# Talko_1_2.net
KiCad netlist of a schematic drawn in EAGLE
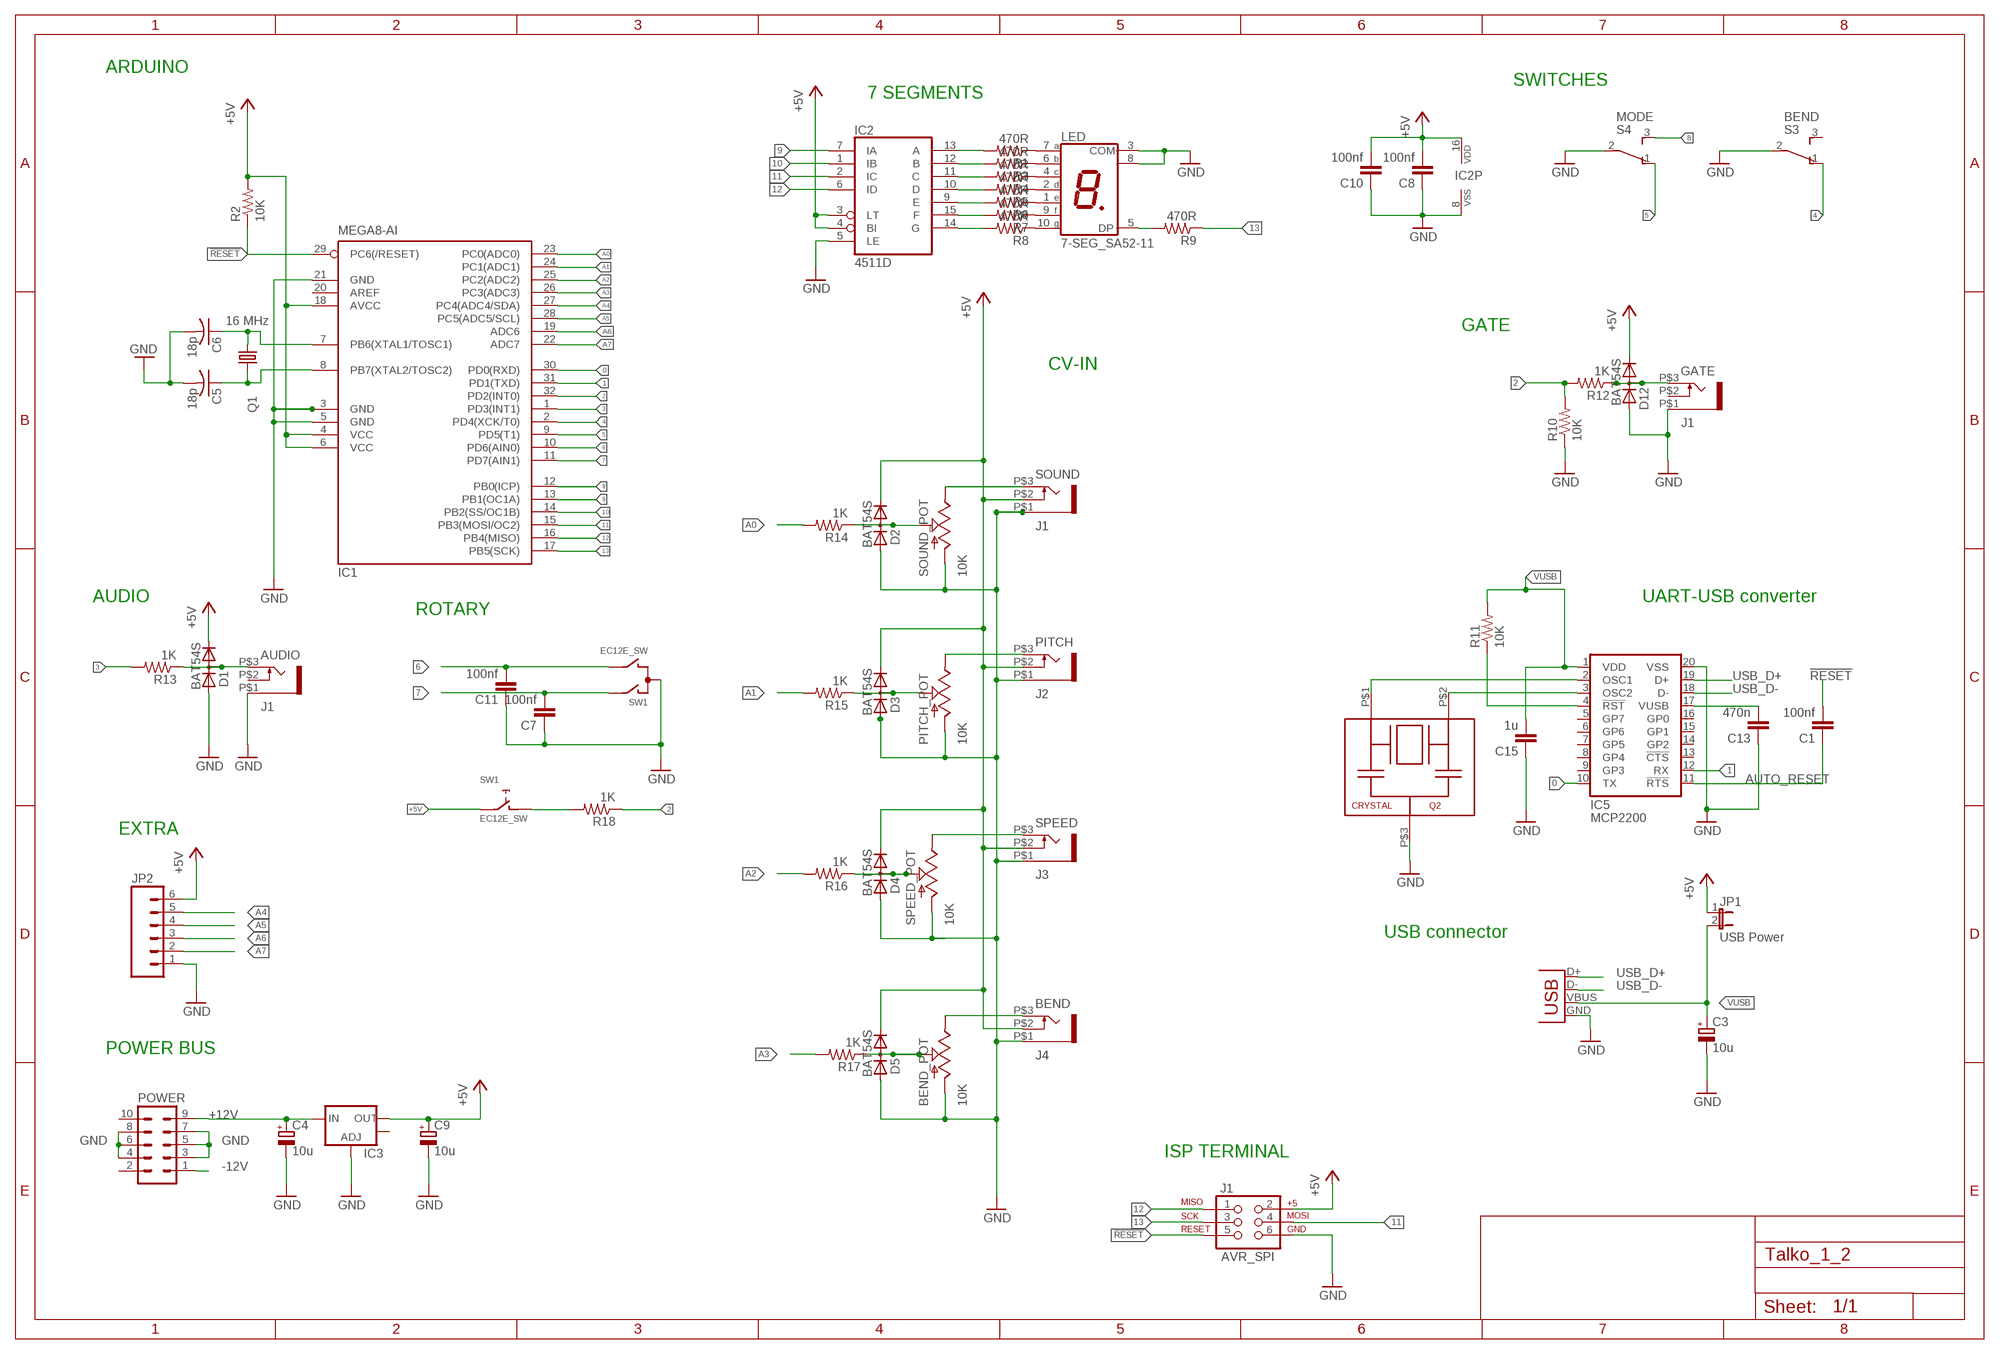
[diagram p0: schematic, sheet 1]

(export (version "E")
  (design (tool "Eeschema 10.0.6"))
  (components
    (comp (ref "AUDIO")
      (value "J1")
      (footprint "eagle-import:THONKICONN")
      (libsource (lib "eagle-import") (part "THONKICONN"))
    )
    (comp (ref "BEND")
      (value "J4")
      (footprint "eagle-import:THONKICONN")
      (libsource (lib "eagle-import") (part "THONKICONN"))
    )
    (comp (ref "BEND_POT")
      (value "10K")
      (footprint "eagle-import:ALPS_POT")
      (libsource (lib "eagle-import") (part "POT"))
    )
    (comp (ref "C1")
      (value "100nf")
      (footprint "eagle-import:C0805")
      (libsource (lib "eagle-import") (part "C-EUC0805"))
    )
    (comp (ref "C3")
      (value "10u")
      (footprint "eagle-import:R_2012-12R")
      (libsource (lib "eagle-import") (part "CPOL-EUR/2012-12R"))
    )
    (comp (ref "C4")
      (value "10u")
      (footprint "eagle-import:R_2012-12R")
      (libsource (lib "eagle-import") (part "CPOL-EUR/2012-12R"))
    )
    (comp (ref "C5")
      (value "18p")
      (footprint "eagle-import:C0805K")
      (libsource (lib "eagle-import") (part "C-USC0805K"))
    )
    (comp (ref "C6")
      (value "18p")
      (footprint "eagle-import:C0805K")
      (libsource (lib "eagle-import") (part "C-USC0805K"))
    )
    (comp (ref "C7")
      (value "100nf")
      (footprint "eagle-import:C0805")
      (libsource (lib "eagle-import") (part "C-EUC0805"))
    )
    (comp (ref "C8")
      (value "100nf")
      (footprint "eagle-import:C0805")
      (libsource (lib "eagle-import") (part "C-EUC0805"))
    )
    (comp (ref "C9")
      (value "10u")
      (footprint "eagle-import:R_2012-12R")
      (libsource (lib "eagle-import") (part "CPOL-EUR/2012-12R"))
    )
    (comp (ref "C10")
      (value "100nf")
      (footprint "eagle-import:C0805")
      (libsource (lib "eagle-import") (part "C-EUC0805"))
    )
    (comp (ref "C11")
      (value "100nf")
      (footprint "eagle-import:C0805")
      (libsource (lib "eagle-import") (part "C-EUC0805"))
    )
    (comp (ref "C13")
      (value "470n")
      (footprint "eagle-import:0805")
      (libsource (lib "eagle-import") (part "CAP0805"))
    )
    (comp (ref "C15")
      (value "1u")
      (footprint "eagle-import:0805")
      (libsource (lib "eagle-import") (part "CAP0805"))
    )
    (comp (ref "D1")
      (value "BAT54S")
      (footprint "eagle-import:SOT23")
      (libsource (lib "eagle-import") (part "DIODE_2CACA-SOT23"))
    )
    (comp (ref "D2")
      (value "BAT54S")
      (footprint "eagle-import:SOT23")
      (libsource (lib "eagle-import") (part "DIODE_2CACA-SOT23"))
    )
    (comp (ref "D3")
      (value "BAT54S")
      (footprint "eagle-import:SOT23")
      (libsource (lib "eagle-import") (part "DIODE_2CACA-SOT23"))
    )
    (comp (ref "D4")
      (value "BAT54S")
      (footprint "eagle-import:SOT23")
      (libsource (lib "eagle-import") (part "DIODE_2CACA-SOT23"))
    )
    (comp (ref "D5")
      (value "BAT54S")
      (footprint "eagle-import:SOT23")
      (libsource (lib "eagle-import") (part "DIODE_2CACA-SOT23"))
    )
    (comp (ref "D12")
      (value "BAT54S")
      (footprint "eagle-import:SOT23")
      (libsource (lib "eagle-import") (part "DIODE_2CACA-SOT23"))
    )
    (comp (ref "GATE")
      (value "J1")
      (footprint "eagle-import:THONKICONN")
      (libsource (lib "eagle-import") (part "THONKICONN"))
    )
    (comp (ref "IC1")
      (value "MEGA8-AI")
      (footprint "eagle-import:TQFP32-08")
      (fields (field (name "MPN") "ATMEGA8-16AU"))
      (libsource (lib "eagle-import") (part "MEGA8-AI"))
    )
    (comp (ref "IC2")
      (value "4511D")
      (footprint "eagle-import:SO16")
      (fields (field (name "OC_MOUSER") "863-MC14511BDG"))
      (libsource (lib "eagle-import") (part "4511D"))
    )
    (comp (ref "IC3")
      (value "V_REG_LM1117SOT223")
      (footprint "eagle-import:SOT223")
      (libsource (lib "eagle-import") (part "V_REG_LM1117SOT223"))
    )
    (comp (ref "IC5")
      (value "MCP2200")
      (footprint "eagle-import:SO20")
      (libsource (lib "eagle-import") (part "MCP2200"))
    )
    (comp (ref "J1")
      (value "AVR_SPI")
      (footprint "eagle-import:2X3_LOCK")
      (libsource (lib "eagle-import") (part "AVR_SPI_PRG_62X3_LOCK"))
    )
    (comp (ref "JP1")
      (value "USB Power")
      (footprint "eagle-import:JP1")
      (libsource (lib "eagle-import") (part "JP1E"))
    )
    (comp (ref "JP2")
      (value "M06SIP")
      (footprint "eagle-import:1X06")
      (libsource (lib "eagle-import") (part "M06SIP"))
    )
    (comp (ref "LED")
      (value "7-SEG_SA52-11")
      (footprint "eagle-import:SA52-11")
      (fields (field (name "OC_FARNELL") "1168602"))
      (libsource (lib "eagle-import") (part "7-SEG_SA52-11"))
    )
    (comp (ref "PITCH")
      (value "J2")
      (footprint "eagle-import:THONKICONN")
      (libsource (lib "eagle-import") (part "THONKICONN"))
    )
    (comp (ref "PITCH_POT")
      (value "10K")
      (footprint "eagle-import:ALPS_POT")
      (libsource (lib "eagle-import") (part "POT"))
    )
    (comp (ref "POWER")
      (value "10_PIN_HEADER")
      (footprint "eagle-import:MA05-2")
      (libsource (lib "eagle-import") (part "10_PIN_HEADER"))
    )
    (comp (ref "Q1")
      (value "16 MHz")
      (footprint "eagle-import:CTS406")
      (libsource (lib "eagle-import") (part "CRYSTALCTS406"))
    )
    (comp (ref "Q2")
      (value "CRYSTAL")
      (footprint "eagle-import:CRYSTAL")
      (libsource (lib "eagle-import") (part "CRYSTAL"))
    )
    (comp (ref "R1")
      (value "470R")
      (footprint "eagle-import:M0805")
      (libsource (lib "eagle-import") (part "R-US_M0805"))
    )
    (comp (ref "R2")
      (value "10K")
      (footprint "eagle-import:M0805")
      (libsource (lib "eagle-import") (part "R-US_M0805"))
    )
    (comp (ref "R3")
      (value "470R")
      (footprint "eagle-import:M0805")
      (libsource (lib "eagle-import") (part "R-US_M0805"))
    )
    (comp (ref "R4")
      (value "470R")
      (footprint "eagle-import:M0805")
      (libsource (lib "eagle-import") (part "R-US_M0805"))
    )
    (comp (ref "R5")
      (value "470R")
      (footprint "eagle-import:M0805")
      (libsource (lib "eagle-import") (part "R-US_M0805"))
    )
    (comp (ref "R6")
      (value "470R")
      (footprint "eagle-import:M0805")
      (libsource (lib "eagle-import") (part "R-US_M0805"))
    )
    (comp (ref "R7")
      (value "470R")
      (footprint "eagle-import:M0805")
      (libsource (lib "eagle-import") (part "R-US_M0805"))
    )
    (comp (ref "R8")
      (value "470R")
      (footprint "eagle-import:M0805")
      (libsource (lib "eagle-import") (part "R-US_M0805"))
    )
    (comp (ref "R9")
      (value "470R")
      (footprint "eagle-import:M0805")
      (libsource (lib "eagle-import") (part "R-US_M0805"))
    )
    (comp (ref "R10")
      (value "10K")
      (footprint "eagle-import:M0805")
      (libsource (lib "eagle-import") (part "R-US_M0805"))
    )
    (comp (ref "R11")
      (value "10K")
      (footprint "eagle-import:M0805")
      (libsource (lib "eagle-import") (part "R-US_M0805"))
    )
    (comp (ref "R12")
      (value "1K")
      (footprint "eagle-import:M0805")
      (libsource (lib "eagle-import") (part "R-US_M0805"))
    )
    (comp (ref "R13")
      (value "1K")
      (footprint "eagle-import:M0805")
      (libsource (lib "eagle-import") (part "R-US_M0805"))
    )
    (comp (ref "R14")
      (value "1K")
      (footprint "eagle-import:M0805")
      (libsource (lib "eagle-import") (part "R-US_M0805"))
    )
    (comp (ref "R15")
      (value "1K")
      (footprint "eagle-import:M0805")
      (libsource (lib "eagle-import") (part "R-US_M0805"))
    )
    (comp (ref "R16")
      (value "1K")
      (footprint "eagle-import:M0805")
      (libsource (lib "eagle-import") (part "R-US_M0805"))
    )
    (comp (ref "R17")
      (value "1K")
      (footprint "eagle-import:M0805")
      (libsource (lib "eagle-import") (part "R-US_M0805"))
    )
    (comp (ref "R18")
      (value "1K")
      (footprint "eagle-import:M0805")
      (libsource (lib "eagle-import") (part "R-US_M0805"))
    )
    (comp (ref "S3")
      (value "BEND")
      (footprint "eagle-import:TL3XPO")
      (libsource (lib "eagle-import") (part "TL36PO"))
    )
    (comp (ref "S4")
      (value "MODE")
      (footprint "eagle-import:TL3XPO")
      (libsource (lib "eagle-import") (part "TL36PO"))
    )
    (comp (ref "SOUND")
      (value "J1")
      (footprint "eagle-import:THONKICONN")
      (libsource (lib "eagle-import") (part "THONKICONN"))
    )
    (comp (ref "SOUND_POT")
      (value "10K")
      (footprint "eagle-import:ALPS_POT")
      (libsource (lib "eagle-import") (part "POT"))
    )
    (comp (ref "SPEED")
      (value "J3")
      (footprint "eagle-import:THONKICONN")
      (libsource (lib "eagle-import") (part "THONKICONN"))
    )
    (comp (ref "SPEED_POT")
      (value "10K")
      (footprint "eagle-import:ALPS_POT")
      (libsource (lib "eagle-import") (part "POT"))
    )
    (comp (ref "SW1")
      (value "EC12E_SW")
      (footprint "eagle-import:ALPS_EC12E_SW")
      (fields (field (name "MPN") "EC12E2424407") (field (name "OC_MOUSER") " PEC11R-4215K-S0024"))
      (libsource (lib "eagle-import") (part "EC12E_SW"))
    )
    (comp (ref "X3")
      (value "USB")
      (footprint "eagle-import:USB-B-PTH-VERTICAL")
      (libsource (lib "eagle-import") (part "USBPTH-VERTICAL"))
    )
  )
  (nets
    (net (code "1") (name "+5V") (class "Default")
      (node (ref "BEND") (pin "P$2") (pinfunction "4_P$2") (pintype "passive"))
      (node (ref "C10") (pin "2") (pinfunction "2_2") (pintype "passive"))
      (node (ref "C8") (pin "2") (pinfunction "2_2") (pintype "passive"))
      (node (ref "C9") (pin "+") (pinfunction "+_+") (pintype "passive"))
      (node (ref "D1") (pin "2") (pinfunction "C_2") (pintype "passive"))
      (node (ref "D12") (pin "2") (pinfunction "C_2") (pintype "passive"))
      (node (ref "D2") (pin "2") (pinfunction "C_2") (pintype "passive"))
      (node (ref "D3") (pin "2") (pinfunction "C_2") (pintype "passive"))
      (node (ref "D4") (pin "2") (pinfunction "C_2") (pintype "passive"))
      (node (ref "D5") (pin "2") (pinfunction "C_2") (pintype "passive"))
      (node (ref "IC1") (pin "18") (pinfunction "AVCC_18") (pintype "power_in"))
      (node (ref "IC1") (pin "4") (pinfunction "VCC_4") (pintype "power_in"))
      (node (ref "IC1") (pin "6") (pinfunction "VCC_6") (pintype "power_in"))
      (node (ref "IC2") (pin "16") (pinfunction "VDD_16") (pintype "power_in"))
      (node (ref "IC2") (pin "3") (pinfunction "LT_3") (pintype "input"))
      (node (ref "IC2") (pin "4") (pinfunction "BI_4") (pintype "input"))
      (node (ref "IC3") (pin "2") (pinfunction "OUT_2") (pintype "output"))
      (node (ref "J1") (pin "2") (pinfunction "2_2") (pintype "passive"))
      (node (ref "JP1") (pin "1") (pinfunction "1_1") (pintype "passive"))
      (node (ref "JP2") (pin "6") (pinfunction "6_6") (pintype "passive"))
      (node (ref "PITCH") (pin "P$2") (pinfunction "4_P$2") (pintype "passive"))
      (node (ref "R2") (pin "2") (pinfunction "2_2") (pintype "passive"))
      (node (ref "SOUND") (pin "P$2") (pinfunction "4_P$2") (pintype "passive"))
      (node (ref "SPEED") (pin "P$2") (pinfunction "4_P$2") (pintype "passive"))
      (node (ref "SW1") (pin "E") (pinfunction "2_E") (pintype "passive"))
    )
    (net (code "2") (name "/+12V") (class "Default")
      (node (ref "C4") (pin "+") (pinfunction "+_+") (pintype "passive"))
      (node (ref "IC3") (pin "3") (pinfunction "IN_3") (pintype "input"))
      (node (ref "POWER") (pin "9") (pinfunction "9_9") (pintype "passive"))
    )
    (net (code "3") (name "/-12V") (class "Default")
      (node (ref "POWER") (pin "1") (pinfunction "1_1") (pintype "passive"))
    )
    (net (code "4") (name "/AUTO_RESET") (class "Default")
      (node (ref "C1") (pin "1") (pinfunction "1_1") (pintype "passive"))
      (node (ref "IC5") (pin "11") (pinfunction "~{RTS}_11") (pintype "bidirectional"))
    )
    (net (code "5") (name "/USB_D+") (class "Default")
      (node (ref "IC5") (pin "19") (pinfunction "D+_19") (pintype "bidirectional"))
      (node (ref "X3") (pin "D+") (pinfunction "D+_D+") (pintype "bidirectional"))
    )
    (net (code "6") (name "/USB_D-") (class "Default")
      (node (ref "IC5") (pin "18") (pinfunction "D-_18") (pintype "bidirectional"))
      (node (ref "X3") (pin "D-") (pinfunction "D-_D-") (pintype "bidirectional"))
    )
    (net (code "7") (name "/~{RESET}") (class "Default")
      (node (ref "C1") (pin "2") (pinfunction "2_2") (pintype "passive"))
      (node (ref "IC1") (pin "29") (pinfunction "PC6(/RESET)_29") (pintype "bidirectional"))
      (node (ref "J1") (pin "5") (pinfunction "5_5") (pintype "passive"))
      (node (ref "R2") (pin "1") (pinfunction "1_1") (pintype "passive"))
    )
    (net (code "8") (name "0") (class "Default")
      (node (ref "IC1") (pin "30") (pinfunction "PD0(RXD)_30") (pintype "bidirectional"))
      (node (ref "IC5") (pin "10") (pinfunction "TX_10") (pintype "bidirectional"))
    )
    (net (code "9") (name "1") (class "Default")
      (node (ref "IC1") (pin "31") (pinfunction "PD1(TXD)_31") (pintype "bidirectional"))
      (node (ref "IC5") (pin "12") (pinfunction "RX_12") (pintype "bidirectional"))
    )
    (net (code "10") (name "2") (class "Default")
      (node (ref "IC1") (pin "32") (pinfunction "PD2(INT0)_32") (pintype "bidirectional"))
      (node (ref "R10") (pin "2") (pinfunction "2_2") (pintype "passive"))
      (node (ref "R12") (pin "2") (pinfunction "2_2") (pintype "passive"))
      (node (ref "R18") (pin "1") (pinfunction "1_1") (pintype "passive"))
    )
    (net (code "11") (name "3") (class "Default")
      (node (ref "IC1") (pin "1") (pinfunction "PD3(INT1)_1") (pintype "bidirectional"))
      (node (ref "R13") (pin "2") (pinfunction "2_2") (pintype "passive"))
    )
    (net (code "12") (name "4") (class "Default")
      (node (ref "IC1") (pin "2") (pinfunction "PD4(XCK/T0)_2") (pintype "bidirectional"))
      (node (ref "S3") (pin "1") (pinfunction "O_1") (pintype "passive"))
    )
    (net (code "13") (name "5") (class "Default")
      (node (ref "IC1") (pin "9") (pinfunction "PD5(T1)_9") (pintype "bidirectional"))
      (node (ref "S4") (pin "1") (pinfunction "O_1") (pintype "passive"))
    )
    (net (code "14") (name "6") (class "Default")
      (node (ref "C11") (pin "2") (pinfunction "2_2") (pintype "passive"))
      (node (ref "IC1") (pin "10") (pinfunction "PD6(AIN0)_10") (pintype "bidirectional"))
      (node (ref "SW1") (pin "B") (pinfunction "B_B") (pintype "passive"))
    )
    (net (code "15") (name "7") (class "Default")
      (node (ref "C7") (pin "2") (pinfunction "2_2") (pintype "passive"))
      (node (ref "IC1") (pin "11") (pinfunction "PD7(AIN1)_11") (pintype "bidirectional"))
      (node (ref "SW1") (pin "A") (pinfunction "A_A") (pintype "passive"))
    )
    (net (code "16") (name "8") (class "Default")
      (node (ref "IC1") (pin "12") (pinfunction "PB0(ICP)_12") (pintype "bidirectional"))
      (node (ref "S4") (pin "3") (pinfunction "S_3") (pintype "passive"))
    )
    (net (code "17") (name "9") (class "Default")
      (node (ref "IC1") (pin "13") (pinfunction "PB1(OC1A)_13") (pintype "bidirectional"))
      (node (ref "IC2") (pin "7") (pinfunction "IA_7") (pintype "input"))
    )
    (net (code "18") (name "10") (class "Default")
      (node (ref "IC1") (pin "14") (pinfunction "PB2(SS/OC1B)_14") (pintype "bidirectional"))
      (node (ref "IC2") (pin "1") (pinfunction "IB_1") (pintype "input"))
    )
    (net (code "19") (name "11") (class "Default")
      (node (ref "IC1") (pin "15") (pinfunction "PB3(MOSI/OC2)_15") (pintype "bidirectional"))
      (node (ref "IC2") (pin "2") (pinfunction "IC_2") (pintype "input"))
      (node (ref "J1") (pin "4") (pinfunction "4_4") (pintype "passive"))
    )
    (net (code "20") (name "12") (class "Default")
      (node (ref "IC1") (pin "16") (pinfunction "PB4(MISO)_16") (pintype "bidirectional"))
      (node (ref "IC2") (pin "6") (pinfunction "ID_6") (pintype "input"))
      (node (ref "J1") (pin "1") (pinfunction "1_1") (pintype "passive"))
    )
    (net (code "21") (name "13") (class "Default")
      (node (ref "IC1") (pin "17") (pinfunction "PB5(SCK)_17") (pintype "bidirectional"))
      (node (ref "J1") (pin "3") (pinfunction "3_3") (pintype "passive"))
      (node (ref "R9") (pin "1") (pinfunction "1_1") (pintype "passive"))
    )
    (net (code "22") (name "A0") (class "Default")
      (node (ref "IC1") (pin "23") (pinfunction "PC0(ADC0)_23") (pintype "bidirectional"))
      (node (ref "R14") (pin "2") (pinfunction "2_2") (pintype "passive"))
    )
    (net (code "23") (name "A1") (class "Default")
      (node (ref "IC1") (pin "24") (pinfunction "PC1(ADC1)_24") (pintype "bidirectional"))
      (node (ref "R15") (pin "2") (pinfunction "2_2") (pintype "passive"))
    )
    (net (code "24") (name "A2") (class "Default")
      (node (ref "IC1") (pin "25") (pinfunction "PC2(ADC2)_25") (pintype "bidirectional"))
      (node (ref "R16") (pin "2") (pinfunction "2_2") (pintype "passive"))
    )
    (net (code "25") (name "A3") (class "Default")
      (node (ref "IC1") (pin "26") (pinfunction "PC3(ADC3)_26") (pintype "bidirectional"))
      (node (ref "R17") (pin "2") (pinfunction "2_2") (pintype "passive"))
    )
    (net (code "26") (name "A4") (class "Default")
      (node (ref "IC1") (pin "27") (pinfunction "PC4(ADC4/SDA)_27") (pintype "bidirectional"))
      (node (ref "JP2") (pin "5") (pinfunction "5_5") (pintype "passive"))
    )
    (net (code "27") (name "A5") (class "Default")
      (node (ref "IC1") (pin "28") (pinfunction "PC5(ADC5/SCL)_28") (pintype "bidirectional"))
      (node (ref "JP2") (pin "4") (pinfunction "4_4") (pintype "passive"))
    )
    (net (code "28") (name "A6") (class "Default")
      (node (ref "IC1") (pin "19") (pinfunction "ADC6_19") (pintype "bidirectional"))
      (node (ref "JP2") (pin "3") (pinfunction "3_3") (pintype "passive"))
    )
    (net (code "29") (name "A7") (class "Default")
      (node (ref "IC1") (pin "22") (pinfunction "ADC7_22") (pintype "bidirectional"))
      (node (ref "JP2") (pin "2") (pinfunction "2_2") (pintype "passive"))
    )
    (net (code "30") (name "GND") (class "Default")
      (node (ref "AUDIO") (pin "P$1") (pinfunction "5_P$1") (pintype "passive"))
      (node (ref "BEND") (pin "P$1") (pinfunction "5_P$1") (pintype "passive"))
      (node (ref "BEND_POT") (pin "P$3") (pinfunction "A_P$3") (pintype "passive"))
      (node (ref "C10") (pin "1") (pinfunction "1_1") (pintype "passive"))
      (node (ref "C11") (pin "1") (pinfunction "1_1") (pintype "passive"))
      (node (ref "C13") (pin "1") (pinfunction "1_1") (pintype "passive"))
      (node (ref "C15") (pin "1") (pinfunction "1_1") (pintype "passive"))
      (node (ref "C3") (pin "-") (pinfunction "-_-") (pintype "passive"))
      (node (ref "C4") (pin "-") (pinfunction "-_-") (pintype "passive"))
      (node (ref "C5") (pin "2") (pinfunction "2_2") (pintype "passive"))
      (node (ref "C6") (pin "2") (pinfunction "2_2") (pintype "passive"))
      (node (ref "C7") (pin "1") (pinfunction "1_1") (pintype "passive"))
      (node (ref "C8") (pin "1") (pinfunction "1_1") (pintype "passive"))
      (node (ref "C9") (pin "-") (pinfunction "-_-") (pintype "passive"))
      (node (ref "D1") (pin "1") (pinfunction "A_1") (pintype "passive"))
      (node (ref "D12") (pin "1") (pinfunction "A_1") (pintype "passive"))
      (node (ref "D2") (pin "1") (pinfunction "A_1") (pintype "passive"))
      (node (ref "D3") (pin "1") (pinfunction "A_1") (pintype "passive"))
      (node (ref "D4") (pin "1") (pinfunction "A_1") (pintype "passive"))
      (node (ref "D5") (pin "1") (pinfunction "A_1") (pintype "passive"))
      (node (ref "GATE") (pin "P$1") (pinfunction "5_P$1") (pintype "passive"))
      (node (ref "IC1") (pin "21") (pinfunction "GND_21") (pintype "power_in"))
      (node (ref "IC1") (pin "3") (pinfunction "GND_3") (pintype "power_in"))
      (node (ref "IC1") (pin "5") (pinfunction "GND_5") (pintype "power_in"))
      (node (ref "IC2") (pin "5") (pinfunction "LE_5") (pintype "input"))
      (node (ref "IC2") (pin "8") (pinfunction "VSS_8") (pintype "power_in"))
      (node (ref "IC3") (pin "1") (pinfunction "ADJ_1") (pintype "input"))
      (node (ref "IC5") (pin "20") (pinfunction "VSS_20") (pintype "power_in"))
      (node (ref "J1") (pin "6") (pinfunction "6_6") (pintype "passive"))
      (node (ref "JP2") (pin "1") (pinfunction "1_1") (pintype "passive"))
      (node (ref "LED") (pin "3") (pinfunction "COM_3") (pintype "passive"))
      (node (ref "LED") (pin "8") (pinfunction "COM_8") (pintype "passive"))
      (node (ref "PITCH") (pin "P$1") (pinfunction "5_P$1") (pintype "passive"))
      (node (ref "PITCH_POT") (pin "P$3") (pinfunction "A_P$3") (pintype "passive"))
      (node (ref "POWER") (pin "3") (pinfunction "3_3") (pintype "passive"))
      (node (ref "POWER") (pin "4") (pinfunction "4_4") (pintype "passive"))
      (node (ref "POWER") (pin "5") (pinfunction "5_5") (pintype "passive"))
      (node (ref "POWER") (pin "6") (pinfunction "6_6") (pintype "passive"))
      (node (ref "POWER") (pin "7") (pinfunction "7_7") (pintype "passive"))
      (node (ref "POWER") (pin "8") (pinfunction "8_8") (pintype "passive"))
      (node (ref "Q2") (pin "P$3") (pinfunction "3_P$3") (pintype "bidirectional"))
      (node (ref "R10") (pin "1") (pinfunction "1_1") (pintype "passive"))
      (node (ref "S3") (pin "2") (pinfunction "P_2") (pintype "passive"))
      (node (ref "S4") (pin "2") (pinfunction "P_2") (pintype "passive"))
      (node (ref "SOUND") (pin "P$1") (pinfunction "5_P$1") (pintype "passive"))
      (node (ref "SOUND_POT") (pin "P$3") (pinfunction "A_P$3") (pintype "passive"))
      (node (ref "SPEED") (pin "P$1") (pinfunction "5_P$1") (pintype "passive"))
      (node (ref "SPEED_POT") (pin "P$3") (pinfunction "A_P$3") (pintype "passive"))
      (node (ref "SW1") (pin "C") (pinfunction "C_C") (pintype "passive"))
      (node (ref "X3") (pin "GND") (pinfunction "GND_GND") (pintype "bidirectional"))
    )
    (net (code "31") (name "Net-(AUDIO-3)") (class "Default")
      (node (ref "AUDIO") (pin "P$3") (pinfunction "3_P$3") (pintype "passive"))
      (node (ref "D1") (pin "3") (pinfunction "AC_3") (pintype "passive"))
      (node (ref "R13") (pin "1") (pinfunction "1_1") (pintype "passive"))
    )
    (net (code "32") (name "Net-(BEND-3)") (class "Default")
      (node (ref "BEND") (pin "P$3") (pinfunction "3_P$3") (pintype "passive"))
      (node (ref "BEND_POT") (pin "P$1") (pinfunction "E_P$1") (pintype "passive"))
    )
    (net (code "33") (name "Net-(BEND_POT-S)") (class "Default")
      (node (ref "BEND_POT") (pin "P$2") (pinfunction "S_P$2") (pintype "passive"))
      (node (ref "D5") (pin "3") (pinfunction "AC_3") (pintype "passive"))
      (node (ref "R17") (pin "1") (pinfunction "1_1") (pintype "passive"))
    )
    (net (code "34") (name "Net-(D2-AC)") (class "Default")
      (node (ref "D2") (pin "3") (pinfunction "AC_3") (pintype "passive"))
      (node (ref "R14") (pin "1") (pinfunction "1_1") (pintype "passive"))
      (node (ref "SOUND_POT") (pin "P$2") (pinfunction "S_P$2") (pintype "passive"))
    )
    (net (code "35") (name "Net-(D3-AC)") (class "Default")
      (node (ref "D3") (pin "3") (pinfunction "AC_3") (pintype "passive"))
      (node (ref "PITCH_POT") (pin "P$2") (pinfunction "S_P$2") (pintype "passive"))
      (node (ref "R15") (pin "1") (pinfunction "1_1") (pintype "passive"))
    )
    (net (code "36") (name "Net-(D4-AC)") (class "Default")
      (node (ref "D4") (pin "3") (pinfunction "AC_3") (pintype "passive"))
      (node (ref "R16") (pin "1") (pinfunction "1_1") (pintype "passive"))
      (node (ref "SPEED_POT") (pin "P$2") (pinfunction "S_P$2") (pintype "passive"))
    )
    (net (code "37") (name "Net-(D12-AC)") (class "Default")
      (node (ref "D12") (pin "3") (pinfunction "AC_3") (pintype "passive"))
      (node (ref "GATE") (pin "P$3") (pinfunction "3_P$3") (pintype "passive"))
      (node (ref "R12") (pin "1") (pinfunction "1_1") (pintype "passive"))
    )
    (net (code "38") (name "Net-(IC1-PB6(XTAL1{slash}TOSC1))") (class "Default")
      (node (ref "C6") (pin "1") (pinfunction "1_1") (pintype "passive"))
      (node (ref "IC1") (pin "7") (pinfunction "PB6(XTAL1/TOSC1)_7") (pintype "bidirectional"))
      (node (ref "Q1") (pin "3") (pinfunction "2_3") (pintype "passive"))
    )
    (net (code "39") (name "Net-(IC1-PB7(XTAL2{slash}TOSC2))") (class "Default")
      (node (ref "C5") (pin "1") (pinfunction "1_1") (pintype "passive"))
      (node (ref "IC1") (pin "8") (pinfunction "PB7(XTAL2/TOSC2)_8") (pintype "bidirectional"))
      (node (ref "Q1") (pin "1") (pinfunction "1_1") (pintype "passive"))
    )
    (net (code "40") (name "Net-(IC2A-A)") (class "Default")
      (node (ref "IC2") (pin "13") (pinfunction "A_13") (pintype "output"))
      (node (ref "R1") (pin "2") (pinfunction "2_2") (pintype "passive"))
    )
    (net (code "41") (name "Net-(IC2A-B)") (class "Default")
      (node (ref "IC2") (pin "12") (pinfunction "B_12") (pintype "output"))
      (node (ref "R3") (pin "2") (pinfunction "2_2") (pintype "passive"))
    )
    (net (code "42") (name "Net-(IC2A-C)") (class "Default")
      (node (ref "IC2") (pin "11") (pinfunction "C_11") (pintype "output"))
      (node (ref "R4") (pin "2") (pinfunction "2_2") (pintype "passive"))
    )
    (net (code "43") (name "Net-(IC2A-D)") (class "Default")
      (node (ref "IC2") (pin "10") (pinfunction "D_10") (pintype "output"))
      (node (ref "R5") (pin "2") (pinfunction "2_2") (pintype "passive"))
    )
    (net (code "44") (name "Net-(IC2A-E)") (class "Default")
      (node (ref "IC2") (pin "9") (pinfunction "E_9") (pintype "output"))
      (node (ref "R6") (pin "2") (pinfunction "2_2") (pintype "passive"))
    )
    (net (code "45") (name "Net-(IC2A-F)") (class "Default")
      (node (ref "IC2") (pin "15") (pinfunction "F_15") (pintype "output"))
      (node (ref "R7") (pin "2") (pinfunction "2_2") (pintype "passive"))
    )
    (net (code "46") (name "Net-(IC2A-G)") (class "Default")
      (node (ref "IC2") (pin "14") (pinfunction "G_14") (pintype "output"))
      (node (ref "R8") (pin "2") (pinfunction "2_2") (pintype "passive"))
    )
    (net (code "47") (name "Net-(IC5-OSC1)") (class "Default")
      (node (ref "IC5") (pin "2") (pinfunction "OSC1_2") (pintype "bidirectional"))
      (node (ref "Q2") (pin "P$1") (pinfunction "1_P$1") (pintype "bidirectional"))
    )
    (net (code "48") (name "Net-(IC5-OSC2)") (class "Default")
      (node (ref "IC5") (pin "3") (pinfunction "OSC2_3") (pintype "bidirectional"))
      (node (ref "Q2") (pin "P$2") (pinfunction "2_P$2") (pintype "bidirectional"))
    )
    (net (code "49") (name "Net-(IC5-VUSB)") (class "Default")
      (node (ref "C13") (pin "2") (pinfunction "2_2") (pintype "passive"))
      (node (ref "IC5") (pin "17") (pinfunction "VUSB_17") (pintype "bidirectional"))
    )
    (net (code "50") (name "Net-(IC5-~{RST})") (class "Default")
      (node (ref "IC5") (pin "4") (pinfunction "~{RST}_4") (pintype "bidirectional"))
      (node (ref "R11") (pin "1") (pinfunction "1_1") (pintype "passive"))
    )
    (net (code "51") (name "Net-(LED-A)") (class "Default")
      (node (ref "LED") (pin "7") (pinfunction "A_7") (pintype "passive"))
      (node (ref "R1") (pin "1") (pinfunction "1_1") (pintype "passive"))
    )
    (net (code "52") (name "Net-(LED-B)") (class "Default")
      (node (ref "LED") (pin "6") (pinfunction "B_6") (pintype "passive"))
      (node (ref "R3") (pin "1") (pinfunction "1_1") (pintype "passive"))
    )
    (net (code "53") (name "Net-(LED-C)") (class "Default")
      (node (ref "LED") (pin "4") (pinfunction "C_4") (pintype "passive"))
      (node (ref "R4") (pin "1") (pinfunction "1_1") (pintype "passive"))
    )
    (net (code "54") (name "Net-(LED-D)") (class "Default")
      (node (ref "LED") (pin "2") (pinfunction "D_2") (pintype "passive"))
      (node (ref "R5") (pin "1") (pinfunction "1_1") (pintype "passive"))
    )
    (net (code "55") (name "Net-(LED-DP)") (class "Default")
      (node (ref "LED") (pin "5") (pinfunction "DP_5") (pintype "passive"))
      (node (ref "R9") (pin "2") (pinfunction "2_2") (pintype "passive"))
    )
    (net (code "56") (name "Net-(LED-E)") (class "Default")
      (node (ref "LED") (pin "1") (pinfunction "E_1") (pintype "passive"))
      (node (ref "R6") (pin "1") (pinfunction "1_1") (pintype "passive"))
    )
    (net (code "57") (name "Net-(LED-F)") (class "Default")
      (node (ref "LED") (pin "9") (pinfunction "F_9") (pintype "passive"))
      (node (ref "R7") (pin "1") (pinfunction "1_1") (pintype "passive"))
    )
    (net (code "58") (name "Net-(LED-G)") (class "Default")
      (node (ref "LED") (pin "10") (pinfunction "G_10") (pintype "passive"))
      (node (ref "R8") (pin "1") (pinfunction "1_1") (pintype "passive"))
    )
    (net (code "59") (name "Net-(PITCH-3)") (class "Default")
      (node (ref "PITCH") (pin "P$3") (pinfunction "3_P$3") (pintype "passive"))
      (node (ref "PITCH_POT") (pin "P$1") (pinfunction "E_P$1") (pintype "passive"))
    )
    (net (code "60") (name "Net-(SOUND-3)") (class "Default")
      (node (ref "SOUND") (pin "P$3") (pinfunction "3_P$3") (pintype "passive"))
      (node (ref "SOUND_POT") (pin "P$1") (pinfunction "E_P$1") (pintype "passive"))
    )
    (net (code "61") (name "Net-(SPEED-3)") (class "Default")
      (node (ref "SPEED") (pin "P$3") (pinfunction "3_P$3") (pintype "passive"))
      (node (ref "SPEED_POT") (pin "P$1") (pinfunction "E_P$1") (pintype "passive"))
    )
    (net (code "62") (name "Net-(SW1B-1)") (class "Default")
      (node (ref "R18") (pin "2") (pinfunction "2_2") (pintype "passive"))
      (node (ref "SW1") (pin "D") (pinfunction "1_D") (pintype "passive"))
    )
    (net (code "63") (name "VUSB") (class "Default")
      (node (ref "C15") (pin "2") (pinfunction "2_2") (pintype "passive"))
      (node (ref "C3") (pin "+") (pinfunction "+_+") (pintype "passive"))
      (node (ref "IC5") (pin "1") (pinfunction "VDD_1") (pintype "power_in"))
      (node (ref "JP1") (pin "2") (pinfunction "2_2") (pintype "passive"))
      (node (ref "R11") (pin "2") (pinfunction "2_2") (pintype "passive"))
      (node (ref "X3") (pin "VBUS") (pinfunction "VBUS_VBUS") (pintype "bidirectional"))
    )
    (net (code "64") (name "unconnected-(AUDIO-4-PadP$2)") (class "Default")
      (node (ref "AUDIO") (pin "P$2") (pinfunction "4_P$2") (pintype "passive"))
    )
    (net (code "65") (name "unconnected-(GATE-4-PadP$2)") (class "Default")
      (node (ref "GATE") (pin "P$2") (pinfunction "4_P$2") (pintype "passive"))
    )
    (net (code "66") (name "unconnected-(IC1-AREF-Pad20)") (class "Default")
      (node (ref "IC1") (pin "20") (pinfunction "AREF_20") (pintype "passive"))
    )
    (net (code "67") (name "unconnected-(IC3-OUT-Pad4)") (class "Default")
      (node (ref "IC3") (pin "4") (pinfunction "OUT_4") (pintype "output"))
    )
    (net (code "68") (name "unconnected-(IC5-GP0-Pad16)") (class "Default")
      (node (ref "IC5") (pin "16") (pinfunction "GP0_16") (pintype "bidirectional"))
    )
    (net (code "69") (name "unconnected-(IC5-GP1-Pad15)") (class "Default")
      (node (ref "IC5") (pin "15") (pinfunction "GP1_15") (pintype "bidirectional"))
    )
    (net (code "70") (name "unconnected-(IC5-GP2-Pad14)") (class "Default")
      (node (ref "IC5") (pin "14") (pinfunction "GP2_14") (pintype "bidirectional"))
    )
    (net (code "71") (name "unconnected-(IC5-GP3-Pad9)") (class "Default")
      (node (ref "IC5") (pin "9") (pinfunction "GP3_9") (pintype "bidirectional"))
    )
    (net (code "72") (name "unconnected-(IC5-GP4-Pad8)") (class "Default")
      (node (ref "IC5") (pin "8") (pinfunction "GP4_8") (pintype "bidirectional"))
    )
    (net (code "73") (name "unconnected-(IC5-GP5-Pad7)") (class "Default")
      (node (ref "IC5") (pin "7") (pinfunction "GP5_7") (pintype "bidirectional"))
    )
    (net (code "74") (name "unconnected-(IC5-GP6-Pad6)") (class "Default")
      (node (ref "IC5") (pin "6") (pinfunction "GP6_6") (pintype "bidirectional"))
    )
    (net (code "75") (name "unconnected-(IC5-GP7-Pad5)") (class "Default")
      (node (ref "IC5") (pin "5") (pinfunction "GP7_5") (pintype "bidirectional"))
    )
    (net (code "76") (name "unconnected-(IC5-~{CTS}-Pad13)") (class "Default")
      (node (ref "IC5") (pin "13") (pinfunction "~{CTS}_13") (pintype "bidirectional"))
    )
    (net (code "77") (name "unconnected-(POWER-Pad2)") (class "Default")
      (node (ref "POWER") (pin "2") (pinfunction "2_2") (pintype "passive"))
    )
    (net (code "78") (name "unconnected-(POWER-Pad10)") (class "Default")
      (node (ref "POWER") (pin "10") (pinfunction "10_10") (pintype "passive"))
    )
    (net (code "79") (name "unconnected-(S3-S-Pad3)") (class "Default")
      (node (ref "S3") (pin "3") (pinfunction "S_3") (pintype "passive"))
    )
  )
)
